# 3_waffling60-SE_mcu.net
KiCad netlist of a schematic drawn in Altium Designer
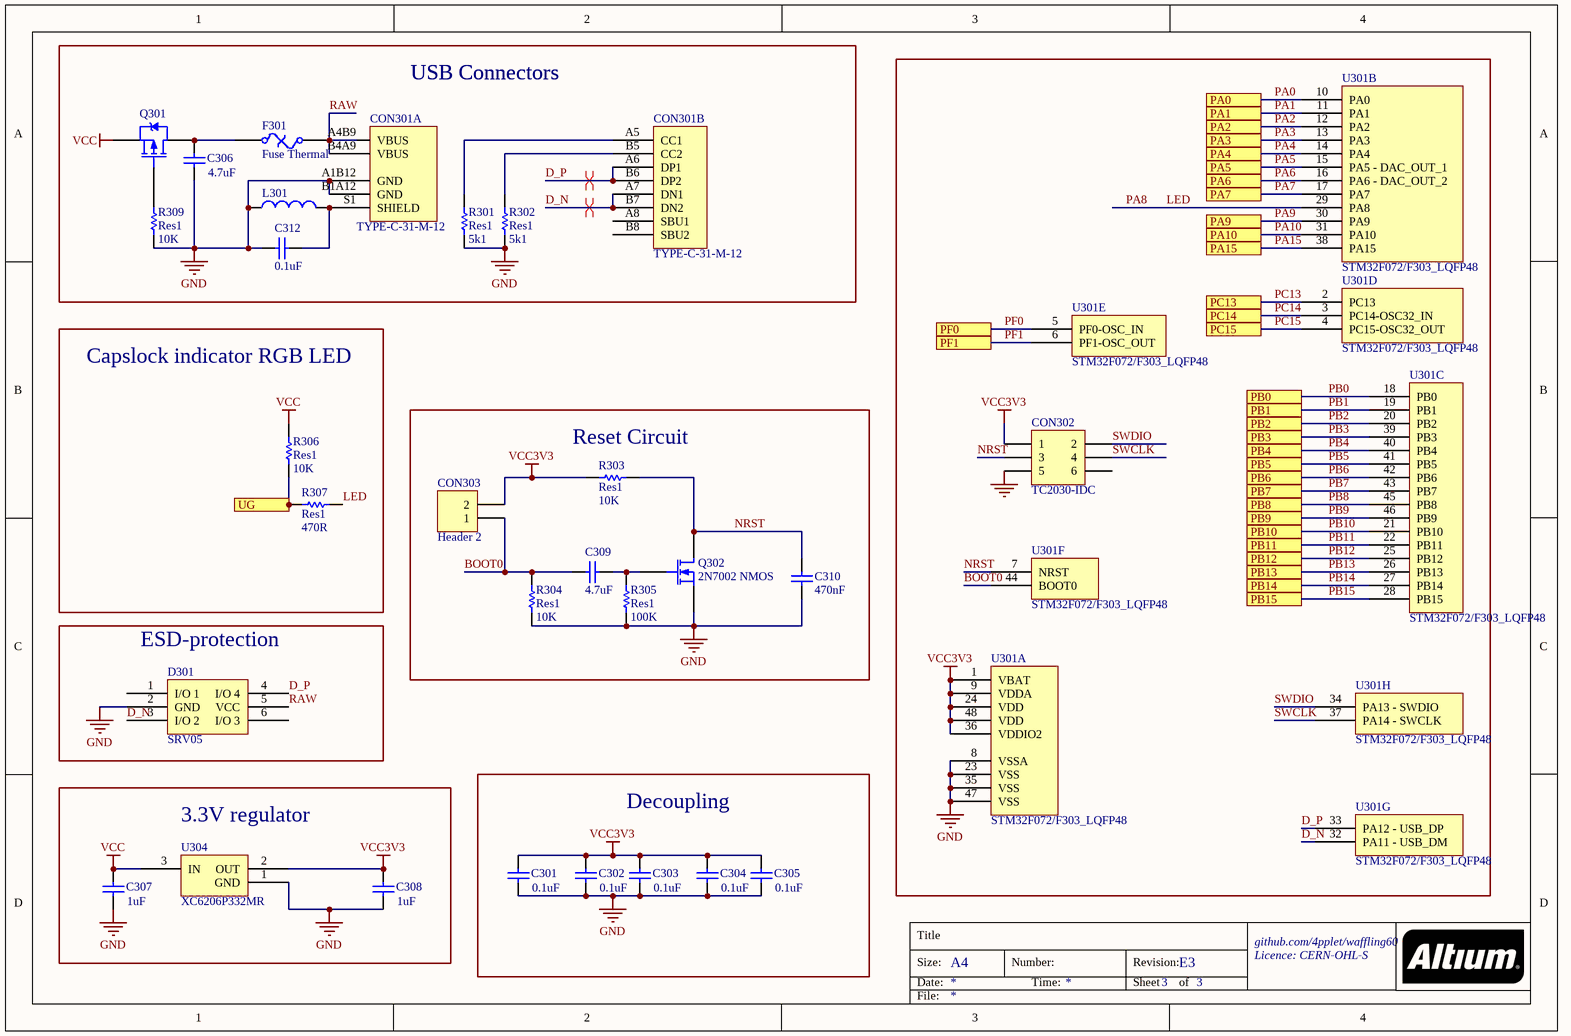
[diagram p0: 3_waffling60-SE_mcu.SchDoc]

(export (version "E")
  (design (tool "Eeschema 10.0.6"))
  (components
    (comp (ref "C301")
      (value "0.1uF")
      (footprint "C0603[1608]")
      (description "Capacitor")
      (fields (field (name "LCSC PART #") "C14663") (field (name "MRF.PART") "CC0603KRX7R9BB104"))
      (libsource (lib "Miscellaneous Devices") (part "Cap"))
    )
    (comp (ref "C302")
      (value "0.1uF")
      (footprint "C0603[1608]")
      (description "Capacitor")
      (fields (field (name "LCSC PART #") "C14663") (field (name "MRF.PART") "CC0603KRX7R9BB104"))
      (libsource (lib "Miscellaneous Devices") (part "Cap"))
    )
    (comp (ref "C303")
      (value "0.1uF")
      (footprint "C0603[1608]")
      (description "Capacitor")
      (fields (field (name "LCSC PART #") "C14663") (field (name "MRF.PART") "CC0603KRX7R9BB104"))
      (libsource (lib "Miscellaneous Devices") (part "Cap"))
    )
    (comp (ref "C304")
      (value "0.1uF")
      (footprint "C0603[1608]")
      (description "Capacitor")
      (fields (field (name "LCSC PART #") "C14663") (field (name "MRF.PART") "CC0603KRX7R9BB104"))
      (libsource (lib "Miscellaneous Devices") (part "Cap"))
    )
    (comp (ref "C305")
      (value "0.1uF")
      (footprint "C0603[1608]")
      (description "Capacitor")
      (fields (field (name "LCSC PART #") "C14663") (field (name "MRF.PART") "CC0603KRX7R9BB104"))
      (libsource (lib "Miscellaneous Devices") (part "Cap"))
    )
    (comp (ref "C306")
      (value "4.7uF")
      (footprint "C0603[1608]")
      (description "Capacitor")
      (fields (field (name "LCSC PART #") "C19666") (field (name "MRF.PART") "CL10A475KO8NNNC"))
      (libsource (lib "Miscellaneous Devices") (part "Cap"))
    )
    (comp (ref "C307")
      (value "1uF")
      (footprint "C0603[1608]")
      (description "Capacitor")
      (fields (field (name "LCSC PART #") "C15849") (field (name "MRF.PART") "CL10A105KB8NNNC"))
      (libsource (lib "Miscellaneous Devices") (part "Cap"))
    )
    (comp (ref "C308")
      (value "1uF")
      (footprint "C0603[1608]")
      (description "Capacitor")
      (fields (field (name "LCSC PART #") "C15849") (field (name "MRF.PART") "CL10A105KB8NNNC"))
      (libsource (lib "Miscellaneous Devices") (part "Cap"))
    )
    (comp (ref "C309")
      (value "4.7uF")
      (footprint "C0603[1608]")
      (description "Capacitor")
      (fields (field (name "LCSC PART #") "C19666") (field (name "MRF.PART") "CL10A475KO8NNNC"))
      (libsource (lib "Miscellaneous Devices") (part "Cap"))
    )
    (comp (ref "C310")
      (value "470nF")
      (footprint "C0603[1608]")
      (description "Capacitor")
      (fields (field (name "LCSC PART #") "C1623") (field (name "MRF.PART") "CL10B474KA8NNNC"))
      (libsource (lib "Miscellaneous Devices") (part "Cap"))
    )
    (comp (ref "C312")
      (value "0.1uF")
      (footprint "C0603[1608]")
      (description "Capacitor")
      (fields (field (name "LCSC PART #") "C14663") (field (name "MRF.PART") "CC0603KRX7R9BB104"))
      (libsource (lib "Miscellaneous Devices") (part "Cap"))
    )
    (comp (ref "CON301")
      (value "TYPE-C-31-M-12")
      (footprint "TYPE-C-31-M-12")
      (fields (field (name "LCSC PART #") "C165948"))
      (libsource (lib "Schlib1") (part "TYPE-C-31-M-12"))
    )
    (comp (ref "CON302")
      (value "TC2030-IDC")
      (footprint "TC2030-IDC-NL")
      (description "Header, 3-Pin, Dual row")
      (libsource (lib "Miscellaneous Connectors") (part "Header 3X2"))
    )
    (comp (ref "CON303")
      (value "Header 2")
      (footprint "HDR1X2")
      (description "Header, 2-Pin")
      (libsource (lib "Miscellaneous Connectors") (part "Header 2"))
    )
    (comp (ref "D301")
      (value "SRV05")
      (footprint "SOT-23-6")
      (fields (field (name "LCSC PART #") "C85364") (field (name "MRF.PART") "SRV05-4-P-T7"))
      (libsource (lib "Keebs") (part "SRV05"))
    )
    (comp (ref "F301")
      (value "Fuse Thermal")
      (footprint "C1206[3216]")
      (description "Thermal Fuse")
      (fields (field (name "LCSC PART #") "C135338") (field (name "MRF.PART") "ASMD1206-050"))
      (libsource (lib "Miscellaneous Devices") (part "Fuse Thermal"))
    )
    (comp (ref "L301")
      (value "Inductor")
      (footprint "L0805")
      (fields (field (name "LCSC PART #") "C1015") (field (name "MRF.PART") "GZ2012D101TF"))
      (libsource (lib "Simulation Generic Components") (part "Inductor"))
    )
    (comp (ref "Q301")
      (value "PMOS-2")
      (footprint "SOT-23-3")
      (description "P-Channel Power MOSFET")
      (fields (field (name "LCSC PART #") "C10487") (field (name "MRF.PART") "SI2301CDS-T1-GE3"))
      (libsource (lib "Miscellaneous Devices") (part "PMOS-2"))
    )
    (comp (ref "Q302")
      (value "2N7002 NMOS")
      (footprint "SOT-23-3")
      (description "N-Channel MOSFET")
      (fields (field (name "LCSC PART #") "C8545") (field (name "MRF.PART") "2N7002"))
      (libsource (lib "Miscellaneous Devices") (part "MOSFET-N"))
    )
    (comp (ref "R301")
      (value "Res1")
      (footprint "R0603[1608]")
      (description "Resistor")
      (fields
        (field (name "ALTIUM_VALUE") "5k1")
        (field (name "LCSC PART #") "C23186")
        (field (name "MRF.PART") "0603WAF5101T5E")
      )
      (libsource (lib "Miscellaneous Devices") (part "Res1"))
    )
    (comp (ref "R302")
      (value "Res1")
      (footprint "R0603[1608]")
      (description "Resistor")
      (fields
        (field (name "ALTIUM_VALUE") "5k1")
        (field (name "LCSC PART #") "C23186")
        (field (name "MRF.PART") "0603WAF5101T5E")
      )
      (libsource (lib "Miscellaneous Devices") (part "Res1"))
    )
    (comp (ref "R303")
      (value "Res1")
      (footprint "R0603[1608]")
      (description "Resistor")
      (fields
        (field (name "ALTIUM_VALUE") "10K")
        (field (name "LCSC PART #") "C25804")
        (field (name "MRF.PART") "0603WAF1002T5E")
      )
      (libsource (lib "Miscellaneous Devices") (part "Res1"))
    )
    (comp (ref "R304")
      (value "Res1")
      (footprint "R0603[1608]")
      (description "Resistor")
      (fields
        (field (name "ALTIUM_VALUE") "10K")
        (field (name "LCSC PART #") "C25804")
        (field (name "MRF.PART") "0603WAF1002T5E")
      )
      (libsource (lib "Miscellaneous Devices") (part "Res1"))
    )
    (comp (ref "R305")
      (value "Res1")
      (footprint "R0603[1608]")
      (description "Resistor")
      (fields
        (field (name "ALTIUM_VALUE") "100K")
        (field (name "LCSC PART #") "C25803")
        (field (name "MRF.PART") "0603WAF1003T5E")
      )
      (libsource (lib "Miscellaneous Devices") (part "Res1"))
    )
    (comp (ref "R306")
      (value "Res1")
      (footprint "R0603[1608]")
      (description "Resistor")
      (fields
        (field (name "ALTIUM_VALUE") "10K")
        (field (name "LCSC PART #") "C25804")
        (field (name "MRF.PART") "0603WAF1002T5E")
      )
      (libsource (lib "Miscellaneous Devices") (part "Res1"))
    )
    (comp (ref "R307")
      (value "Res1")
      (footprint "R0603[1608]")
      (description "Resistor")
      (fields
        (field (name "ALTIUM_VALUE") "470R")
        (field (name "LCSC PART #") "C23179")
        (field (name "MRF.PART") "0603WAF4700T5E")
      )
      (libsource (lib "Miscellaneous Devices") (part "Res1"))
    )
    (comp (ref "R309")
      (value "Res1")
      (footprint "R0603[1608]")
      (description "Resistor")
      (fields
        (field (name "ALTIUM_VALUE") "10K")
        (field (name "LCSC PART #") "C25804")
        (field (name "MRF.PART") "0603WAF1002T5E")
      )
      (libsource (lib "Miscellaneous Devices") (part "Res1"))
    )
    (comp (ref "U301")
      (value "STM32F072/F303_LQFP48")
      (footprint "STM32 - COMBO 7X7MM")
      (fields (field (name "LCSC PART #") "C915660") (field (name "MRF.PART") "APM32F072CBT6"))
      (libsource (lib "Keebs") (part "STM32F072/F303_LQFP48"))
    )
    (comp (ref "U304")
      (value "XC6206P332MR")
      (footprint "SOT-23-3")
      (fields (field (name "LCSC PART #") "C5446"))
      (libsource (lib "Keebs") (part "SOT23 LDO"))
    )
  )
  (nets
    (net (code "1") (name "/BOOT0") (class "Default")
      (node (ref "C309") (pin "1") (pinfunction "1_1") (pintype "passive"))
      (node (ref "CON303") (pin "1") (pinfunction "1_1") (pintype "passive"))
      (node (ref "R304") (pin "1") (pinfunction "1_1") (pintype "passive"))
      (node (ref "U301") (pin "44") (pinfunction "BOOT0_44") (pintype "passive"))
    )
    (net (code "2") (name "/D_N") (class "Default")
      (node (ref "CON301") (pin "A7") (pinfunction "DN1_A7") (pintype "passive"))
      (node (ref "CON301") (pin "B7") (pinfunction "DN2_B7") (pintype "passive"))
      (node (ref "D301") (pin "3") (pinfunction "I/O_2_3") (pintype "passive"))
      (node (ref "U301") (pin "32") (pinfunction "PA11_-_USB_DM_32") (pintype "passive"))
    )
    (net (code "3") (name "/D_P") (class "Default")
      (node (ref "CON301") (pin "A6") (pinfunction "DP1_A6") (pintype "passive"))
      (node (ref "CON301") (pin "B6") (pinfunction "DP2_B6") (pintype "passive"))
      (node (ref "D301") (pin "4") (pinfunction "I/O_4_4") (pintype "passive"))
      (node (ref "U301") (pin "33") (pinfunction "PA12_-_USB_DP_33") (pintype "passive"))
    )
    (net (code "4") (name "/LED") (class "Default")
      (node (ref "R307") (pin "2") (pinfunction "2_2") (pintype "passive"))
      (node (ref "U301") (pin "29") (pinfunction "PA8_29") (pintype "passive"))
    )
    (net (code "5") (name "/NRST") (class "Default")
      (node (ref "C310") (pin "1") (pinfunction "1_1") (pintype "passive"))
      (node (ref "CON302") (pin "3") (pinfunction "3_3") (pintype "passive"))
      (node (ref "Q302") (pin "3") (pinfunction "D_3") (pintype "passive"))
      (node (ref "R303") (pin "2") (pinfunction "2_2") (pintype "passive"))
      (node (ref "U301") (pin "7") (pinfunction "NRST_7") (pintype "passive"))
    )
    (net (code "6") (name "/PA0") (class "Default")
      (node (ref "U301") (pin "10") (pinfunction "PA0_10") (pintype "passive"))
    )
    (net (code "7") (name "/PA1") (class "Default")
      (node (ref "U301") (pin "11") (pinfunction "PA1_11") (pintype "passive"))
    )
    (net (code "8") (name "/PA2") (class "Default")
      (node (ref "U301") (pin "12") (pinfunction "PA2_12") (pintype "passive"))
    )
    (net (code "9") (name "/PA3") (class "Default")
      (node (ref "U301") (pin "13") (pinfunction "PA3_13") (pintype "passive"))
    )
    (net (code "10") (name "/PA4") (class "Default")
      (node (ref "U301") (pin "14") (pinfunction "PA4_14") (pintype "passive"))
    )
    (net (code "11") (name "/PA5") (class "Default")
      (node (ref "U301") (pin "15") (pinfunction "PA5_-_DAC_OUT_1_15") (pintype "passive"))
    )
    (net (code "12") (name "/PA6") (class "Default")
      (node (ref "U301") (pin "16") (pinfunction "PA6_-_DAC_OUT_2_16") (pintype "passive"))
    )
    (net (code "13") (name "/PA7") (class "Default")
      (node (ref "U301") (pin "17") (pinfunction "PA7_17") (pintype "passive"))
    )
    (net (code "14") (name "/PA9") (class "Default")
      (node (ref "U301") (pin "30") (pinfunction "PA9_30") (pintype "passive"))
    )
    (net (code "15") (name "/PA10") (class "Default")
      (node (ref "U301") (pin "31") (pinfunction "PA10_31") (pintype "passive"))
    )
    (net (code "16") (name "/PA15") (class "Default")
      (node (ref "U301") (pin "38") (pinfunction "PA15_38") (pintype "passive"))
    )
    (net (code "17") (name "/PB0") (class "Default")
      (node (ref "U301") (pin "18") (pinfunction "PB0_18") (pintype "passive"))
    )
    (net (code "18") (name "/PB1") (class "Default")
      (node (ref "U301") (pin "19") (pinfunction "PB1_19") (pintype "passive"))
    )
    (net (code "19") (name "/PB2") (class "Default")
      (node (ref "U301") (pin "20") (pinfunction "PB2_20") (pintype "passive"))
    )
    (net (code "20") (name "/PB3") (class "Default")
      (node (ref "U301") (pin "39") (pinfunction "PB3_39") (pintype "passive"))
    )
    (net (code "21") (name "/PB4") (class "Default")
      (node (ref "U301") (pin "40") (pinfunction "PB4_40") (pintype "passive"))
    )
    (net (code "22") (name "/PB5") (class "Default")
      (node (ref "U301") (pin "41") (pinfunction "PB5_41") (pintype "passive"))
    )
    (net (code "23") (name "/PB6") (class "Default")
      (node (ref "U301") (pin "42") (pinfunction "PB6_42") (pintype "passive"))
    )
    (net (code "24") (name "/PB7") (class "Default")
      (node (ref "U301") (pin "43") (pinfunction "PB7_43") (pintype "passive"))
    )
    (net (code "25") (name "/PB8") (class "Default")
      (node (ref "U301") (pin "45") (pinfunction "PB8_45") (pintype "passive"))
    )
    (net (code "26") (name "/PB9") (class "Default")
      (node (ref "U301") (pin "46") (pinfunction "PB9_46") (pintype "passive"))
    )
    (net (code "27") (name "/PB10") (class "Default")
      (node (ref "U301") (pin "21") (pinfunction "PB10_21") (pintype "passive"))
    )
    (net (code "28") (name "/PB11") (class "Default")
      (node (ref "U301") (pin "22") (pinfunction "PB11_22") (pintype "passive"))
    )
    (net (code "29") (name "/PB12") (class "Default")
      (node (ref "U301") (pin "25") (pinfunction "PB12_25") (pintype "passive"))
    )
    (net (code "30") (name "/PB13") (class "Default")
      (node (ref "U301") (pin "26") (pinfunction "PB13_26") (pintype "passive"))
    )
    (net (code "31") (name "/PB14") (class "Default")
      (node (ref "U301") (pin "27") (pinfunction "PB14_27") (pintype "passive"))
    )
    (net (code "32") (name "/PB15") (class "Default")
      (node (ref "U301") (pin "28") (pinfunction "PB15_28") (pintype "passive"))
    )
    (net (code "33") (name "/PC13") (class "Default")
      (node (ref "U301") (pin "2") (pinfunction "PC13_2") (pintype "passive"))
    )
    (net (code "34") (name "/PC14") (class "Default")
      (node (ref "U301") (pin "3") (pinfunction "PC14-OSC32_IN_3") (pintype "passive"))
    )
    (net (code "35") (name "/PC15") (class "Default")
      (node (ref "U301") (pin "4") (pinfunction "PC15-OSC32_OUT_4") (pintype "passive"))
    )
    (net (code "36") (name "/PF0") (class "Default")
      (node (ref "U301") (pin "5") (pinfunction "PF0-OSC_IN_5") (pintype "passive"))
    )
    (net (code "37") (name "/PF1") (class "Default")
      (node (ref "U301") (pin "6") (pinfunction "PF1-OSC_OUT_6") (pintype "passive"))
    )
    (net (code "38") (name "/RAW") (class "Default")
      (node (ref "CON301") (pin "A4B9") (pinfunction "VBUS_A4B9") (pintype "passive"))
      (node (ref "CON301") (pin "B4A9") (pinfunction "VBUS_B4A9") (pintype "passive"))
      (node (ref "D301") (pin "5") (pinfunction "VCC_5") (pintype "passive"))
      (node (ref "F301") (pin "2") (pinfunction "2_2") (pintype "passive"))
    )
    (net (code "39") (name "/SWCLK") (class "Default")
      (node (ref "CON302") (pin "4") (pinfunction "4_4") (pintype "passive"))
      (node (ref "U301") (pin "37") (pinfunction "PA14_-_SWCLK_37") (pintype "passive"))
    )
    (net (code "40") (name "/SWDIO") (class "Default")
      (node (ref "CON302") (pin "2") (pinfunction "2_2") (pintype "passive"))
      (node (ref "U301") (pin "34") (pinfunction "PA13_-_SWDIO_34") (pintype "passive"))
    )
    (net (code "41") (name "/UG") (class "Default")
      (node (ref "R306") (pin "2") (pinfunction "2_2") (pintype "passive"))
      (node (ref "R307") (pin "1") (pinfunction "1_1") (pintype "passive"))
    )
    (net (code "42") (name "GND") (class "Default")
      (node (ref "C301") (pin "1") (pinfunction "1_1") (pintype "passive"))
      (node (ref "C302") (pin "1") (pinfunction "1_1") (pintype "passive"))
      (node (ref "C303") (pin "1") (pinfunction "1_1") (pintype "passive"))
      (node (ref "C304") (pin "1") (pinfunction "1_1") (pintype "passive"))
      (node (ref "C305") (pin "1") (pinfunction "1_1") (pintype "passive"))
      (node (ref "C306") (pin "1") (pinfunction "1_1") (pintype "passive"))
      (node (ref "C307") (pin "1") (pinfunction "1_1") (pintype "passive"))
      (node (ref "C308") (pin "1") (pinfunction "1_1") (pintype "passive"))
      (node (ref "C310") (pin "2") (pinfunction "2_2") (pintype "passive"))
      (node (ref "C312") (pin "1") (pinfunction "1_1") (pintype "passive"))
      (node (ref "CON301") (pin "A1B12") (pinfunction "GND_A1B12") (pintype "passive"))
      (node (ref "CON301") (pin "B1A12") (pinfunction "GND_B1A12") (pintype "passive"))
      (node (ref "CON302") (pin "5") (pinfunction "5_5") (pintype "passive"))
      (node (ref "D301") (pin "2") (pinfunction "GND_2") (pintype "passive"))
      (node (ref "L301") (pin "1") (pinfunction "1_1") (pintype "passive"))
      (node (ref "Q302") (pin "2") (pinfunction "S_2") (pintype "passive"))
      (node (ref "R301") (pin "2") (pinfunction "2_2") (pintype "passive"))
      (node (ref "R302") (pin "2") (pinfunction "2_2") (pintype "passive"))
      (node (ref "R304") (pin "2") (pinfunction "2_2") (pintype "passive"))
      (node (ref "R305") (pin "2") (pinfunction "2_2") (pintype "passive"))
      (node (ref "R309") (pin "2") (pinfunction "2_2") (pintype "passive"))
      (node (ref "U301") (pin "23") (pinfunction "VSS_23") (pintype "passive"))
      (node (ref "U301") (pin "35") (pinfunction "VSS_35") (pintype "passive"))
      (node (ref "U301") (pin "47") (pinfunction "VSS_47") (pintype "passive"))
      (node (ref "U301") (pin "8") (pinfunction "VSSA_8") (pintype "passive"))
      (node (ref "U304") (pin "1") (pinfunction "GND_1") (pintype "passive"))
    )
    (net (code "43") (name "Net-(CON301A-SHIELD)") (class "Default")
      (node (ref "C312") (pin "2") (pinfunction "2_2") (pintype "passive"))
      (node (ref "CON301") (pin "S1") (pinfunction "SHIELD_S1") (pintype "passive"))
      (node (ref "L301") (pin "2") (pinfunction "2_2") (pintype "passive"))
    )
    (net (code "44") (name "Net-(CON301B-CC1)") (class "Default")
      (node (ref "CON301") (pin "A5") (pinfunction "CC1_A5") (pintype "passive"))
      (node (ref "R301") (pin "1") (pinfunction "1_1") (pintype "passive"))
    )
    (net (code "45") (name "Net-(CON301B-CC2)") (class "Default")
      (node (ref "CON301") (pin "B5") (pinfunction "CC2_B5") (pintype "passive"))
      (node (ref "R302") (pin "1") (pinfunction "1_1") (pintype "passive"))
    )
    (net (code "46") (name "Net-(Q301-D)") (class "Default")
      (node (ref "C306") (pin "2") (pinfunction "2_2") (pintype "passive"))
      (node (ref "F301") (pin "1") (pinfunction "1_1") (pintype "passive"))
      (node (ref "Q301") (pin "3") (pinfunction "D_3") (pintype "passive"))
    )
    (net (code "47") (name "Net-(Q301-G)") (class "Default")
      (node (ref "Q301") (pin "1") (pinfunction "G_1") (pintype "passive"))
      (node (ref "R309") (pin "1") (pinfunction "1_1") (pintype "passive"))
    )
    (net (code "48") (name "Net-(Q302-G)") (class "Default")
      (node (ref "C309") (pin "2") (pinfunction "2_2") (pintype "passive"))
      (node (ref "Q302") (pin "1") (pinfunction "G_1") (pintype "passive"))
      (node (ref "R305") (pin "1") (pinfunction "1_1") (pintype "passive"))
    )
    (net (code "49") (name "VCC") (class "Default")
      (node (ref "C307") (pin "2") (pinfunction "2_2") (pintype "passive"))
      (node (ref "Q301") (pin "2") (pinfunction "S_2") (pintype "passive"))
      (node (ref "R306") (pin "1") (pinfunction "1_1") (pintype "passive"))
      (node (ref "U304") (pin "3") (pinfunction "IN_3") (pintype "passive"))
    )
    (net (code "50") (name "VCC3V3") (class "Default")
      (node (ref "C301") (pin "2") (pinfunction "2_2") (pintype "passive"))
      (node (ref "C302") (pin "2") (pinfunction "2_2") (pintype "passive"))
      (node (ref "C303") (pin "2") (pinfunction "2_2") (pintype "passive"))
      (node (ref "C304") (pin "2") (pinfunction "2_2") (pintype "passive"))
      (node (ref "C305") (pin "2") (pinfunction "2_2") (pintype "passive"))
      (node (ref "C308") (pin "2") (pinfunction "2_2") (pintype "passive"))
      (node (ref "CON302") (pin "1") (pinfunction "1_1") (pintype "passive"))
      (node (ref "CON303") (pin "2") (pinfunction "2_2") (pintype "passive"))
      (node (ref "R303") (pin "1") (pinfunction "1_1") (pintype "passive"))
      (node (ref "U301") (pin "1") (pinfunction "VBAT_1") (pintype "passive"))
      (node (ref "U301") (pin "24") (pinfunction "VDD_24") (pintype "passive"))
      (node (ref "U301") (pin "36") (pinfunction "VDDIO2_36") (pintype "passive"))
      (node (ref "U301") (pin "48") (pinfunction "VDD_48") (pintype "passive"))
      (node (ref "U301") (pin "9") (pinfunction "VDDA_9") (pintype "passive"))
      (node (ref "U304") (pin "2") (pinfunction "OUT_2") (pintype "passive"))
    )
    (net (code "51") (name "unconnected-(CON301B-SBU1-PadA8)") (class "Default")
      (node (ref "CON301") (pin "A8") (pinfunction "SBU1_A8") (pintype "passive"))
    )
    (net (code "52") (name "unconnected-(CON301B-SBU2-PadB8)") (class "Default")
      (node (ref "CON301") (pin "B8") (pinfunction "SBU2_B8") (pintype "passive"))
    )
    (net (code "53") (name "unconnected-(CON302-Pad6)") (class "Default")
      (node (ref "CON302") (pin "6") (pinfunction "6_6") (pintype "passive"))
    )
    (net (code "54") (name "unconnected-(D301-I{slash}O_1-Pad1)") (class "Default")
      (node (ref "D301") (pin "1") (pinfunction "I/O_1_1") (pintype "passive"))
    )
    (net (code "55") (name "unconnected-(D301-I{slash}O_3-Pad6)") (class "Default")
      (node (ref "D301") (pin "6") (pinfunction "I/O_3_6") (pintype "passive"))
    )
  )
)
